# Sheet1.net
KiCad netlist of a schematic drawn in Altium Designer
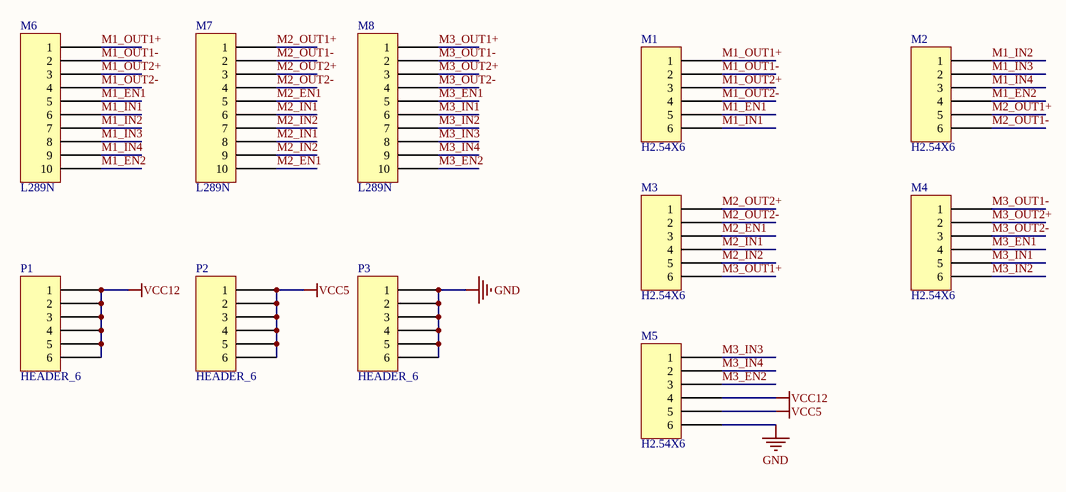
[diagram p0: Sheet1.SchDoc]

(export (version "E")
  (design (tool "Eeschema 10.0.6"))
  (components
    (comp (ref "M1") (value "H2.54X6") (footprint "Header6") (libsource (lib "Schlib1") (part "H2.54X6")))
    (comp (ref "M2") (value "H2.54X6") (footprint "Header6") (libsource (lib "Schlib1") (part "H2.54X6")))
    (comp (ref "M3") (value "H2.54X6") (footprint "Header6") (libsource (lib "Schlib1") (part "H2.54X6")))
    (comp (ref "M4") (value "H2.54X6") (footprint "Header6") (libsource (lib "Schlib1") (part "H2.54X6")))
    (comp (ref "M5") (value "H2.54X6") (footprint "Header6") (libsource (lib "Schlib1") (part "H2.54X6")))
    (comp (ref "M6") (value "L289N") (footprint "HDR1X10") (libsource (lib "Schlib1") (part "L289N")))
    (comp (ref "M7") (value "L289N") (footprint "HDR1X10") (libsource (lib "Schlib1") (part "L289N")))
    (comp (ref "M8") (value "L289N") (footprint "HDR1X10") (libsource (lib "Schlib1") (part "L289N")))
    (comp (ref "P1") (value "HEADER_6") (footprint "HDR1X6") (libsource (lib "Schlib1") (part "HEADER_6")))
    (comp (ref "P2") (value "HEADER_6") (footprint "HDR1X6") (libsource (lib "Schlib1") (part "HEADER_6")))
    (comp (ref "P3") (value "HEADER_6") (footprint "HDR1X6") (libsource (lib "Schlib1") (part "HEADER_6")))
  )
  (nets
    (net (code "1") (name "/M1_EN1") (class "Default")
      (node (ref "M1") (pin "5") (pinfunction "5_5") (pintype "passive"))
      (node (ref "M6") (pin "5") (pinfunction "5_5") (pintype "passive"))
    )
    (net (code "2") (name "/M1_EN2") (class "Default")
      (node (ref "M2") (pin "4") (pinfunction "4_4") (pintype "passive"))
      (node (ref "M6") (pin "10") (pinfunction "10_10") (pintype "passive"))
    )
    (net (code "3") (name "/M1_IN1") (class "Default")
      (node (ref "M1") (pin "6") (pinfunction "6_6") (pintype "passive"))
      (node (ref "M6") (pin "6") (pinfunction "6_6") (pintype "passive"))
    )
    (net (code "4") (name "/M1_IN2") (class "Default")
      (node (ref "M2") (pin "1") (pinfunction "1_1") (pintype "passive"))
      (node (ref "M6") (pin "7") (pinfunction "7_7") (pintype "passive"))
    )
    (net (code "5") (name "/M1_IN3") (class "Default")
      (node (ref "M2") (pin "2") (pinfunction "2_2") (pintype "passive"))
      (node (ref "M6") (pin "8") (pinfunction "8_8") (pintype "passive"))
    )
    (net (code "6") (name "/M1_IN4") (class "Default")
      (node (ref "M2") (pin "3") (pinfunction "3_3") (pintype "passive"))
      (node (ref "M6") (pin "9") (pinfunction "9_9") (pintype "passive"))
    )
    (net (code "7") (name "/M1_OUT1+") (class "Default")
      (node (ref "M1") (pin "1") (pinfunction "1_1") (pintype "passive"))
      (node (ref "M6") (pin "1") (pinfunction "1_1") (pintype "passive"))
    )
    (net (code "8") (name "/M1_OUT1-") (class "Default")
      (node (ref "M1") (pin "2") (pinfunction "2_2") (pintype "passive"))
      (node (ref "M6") (pin "2") (pinfunction "2_2") (pintype "passive"))
    )
    (net (code "9") (name "/M1_OUT2+") (class "Default")
      (node (ref "M1") (pin "3") (pinfunction "3_3") (pintype "passive"))
      (node (ref "M6") (pin "3") (pinfunction "3_3") (pintype "passive"))
    )
    (net (code "10") (name "/M1_OUT2-") (class "Default")
      (node (ref "M1") (pin "4") (pinfunction "4_4") (pintype "passive"))
      (node (ref "M6") (pin "4") (pinfunction "4_4") (pintype "passive"))
    )
    (net (code "11") (name "/M2_EN1") (class "Default")
      (node (ref "M3") (pin "3") (pinfunction "3_3") (pintype "passive"))
      (node (ref "M7") (pin "10") (pinfunction "10_10") (pintype "passive"))
      (node (ref "M7") (pin "5") (pinfunction "5_5") (pintype "passive"))
    )
    (net (code "12") (name "/M2_IN1") (class "Default")
      (node (ref "M3") (pin "4") (pinfunction "4_4") (pintype "passive"))
      (node (ref "M7") (pin "6") (pinfunction "6_6") (pintype "passive"))
      (node (ref "M7") (pin "8") (pinfunction "8_8") (pintype "passive"))
    )
    (net (code "13") (name "/M2_IN2") (class "Default")
      (node (ref "M3") (pin "5") (pinfunction "5_5") (pintype "passive"))
      (node (ref "M7") (pin "7") (pinfunction "7_7") (pintype "passive"))
      (node (ref "M7") (pin "9") (pinfunction "9_9") (pintype "passive"))
    )
    (net (code "14") (name "/M2_OUT1+") (class "Default")
      (node (ref "M2") (pin "5") (pinfunction "5_5") (pintype "passive"))
      (node (ref "M7") (pin "1") (pinfunction "1_1") (pintype "passive"))
    )
    (net (code "15") (name "/M2_OUT1-") (class "Default")
      (node (ref "M2") (pin "6") (pinfunction "6_6") (pintype "passive"))
      (node (ref "M7") (pin "2") (pinfunction "2_2") (pintype "passive"))
    )
    (net (code "16") (name "/M2_OUT2+") (class "Default")
      (node (ref "M3") (pin "1") (pinfunction "1_1") (pintype "passive"))
      (node (ref "M7") (pin "3") (pinfunction "3_3") (pintype "passive"))
    )
    (net (code "17") (name "/M2_OUT2-") (class "Default")
      (node (ref "M3") (pin "2") (pinfunction "2_2") (pintype "passive"))
      (node (ref "M7") (pin "4") (pinfunction "4_4") (pintype "passive"))
    )
    (net (code "18") (name "/M3_EN1") (class "Default")
      (node (ref "M4") (pin "4") (pinfunction "4_4") (pintype "passive"))
      (node (ref "M8") (pin "5") (pinfunction "5_5") (pintype "passive"))
    )
    (net (code "19") (name "/M3_EN2") (class "Default")
      (node (ref "M5") (pin "3") (pinfunction "3_3") (pintype "passive"))
      (node (ref "M8") (pin "10") (pinfunction "10_10") (pintype "passive"))
    )
    (net (code "20") (name "/M3_IN1") (class "Default")
      (node (ref "M4") (pin "5") (pinfunction "5_5") (pintype "passive"))
      (node (ref "M8") (pin "6") (pinfunction "6_6") (pintype "passive"))
    )
    (net (code "21") (name "/M3_IN2") (class "Default")
      (node (ref "M4") (pin "6") (pinfunction "6_6") (pintype "passive"))
      (node (ref "M8") (pin "7") (pinfunction "7_7") (pintype "passive"))
    )
    (net (code "22") (name "/M3_IN3") (class "Default")
      (node (ref "M5") (pin "1") (pinfunction "1_1") (pintype "passive"))
      (node (ref "M8") (pin "8") (pinfunction "8_8") (pintype "passive"))
    )
    (net (code "23") (name "/M3_IN4") (class "Default")
      (node (ref "M5") (pin "2") (pinfunction "2_2") (pintype "passive"))
      (node (ref "M8") (pin "9") (pinfunction "9_9") (pintype "passive"))
    )
    (net (code "24") (name "/M3_OUT1+") (class "Default")
      (node (ref "M3") (pin "6") (pinfunction "6_6") (pintype "passive"))
      (node (ref "M8") (pin "1") (pinfunction "1_1") (pintype "passive"))
    )
    (net (code "25") (name "/M3_OUT1-") (class "Default")
      (node (ref "M4") (pin "1") (pinfunction "1_1") (pintype "passive"))
      (node (ref "M8") (pin "2") (pinfunction "2_2") (pintype "passive"))
    )
    (net (code "26") (name "/M3_OUT2+") (class "Default")
      (node (ref "M4") (pin "2") (pinfunction "2_2") (pintype "passive"))
      (node (ref "M8") (pin "3") (pinfunction "3_3") (pintype "passive"))
    )
    (net (code "27") (name "/M3_OUT2-") (class "Default")
      (node (ref "M4") (pin "3") (pinfunction "3_3") (pintype "passive"))
      (node (ref "M8") (pin "4") (pinfunction "4_4") (pintype "passive"))
    )
    (net (code "28") (name "GND") (class "Default")
      (node (ref "M5") (pin "6") (pinfunction "6_6") (pintype "passive"))
      (node (ref "P3") (pin "1") (pinfunction "1_1") (pintype "passive"))
      (node (ref "P3") (pin "2") (pinfunction "2_2") (pintype "passive"))
      (node (ref "P3") (pin "3") (pinfunction "3_3") (pintype "passive"))
      (node (ref "P3") (pin "4") (pinfunction "4_4") (pintype "passive"))
      (node (ref "P3") (pin "5") (pinfunction "5_5") (pintype "passive"))
      (node (ref "P3") (pin "6") (pinfunction "6_6") (pintype "passive"))
    )
    (net (code "29") (name "VCC5") (class "Default")
      (node (ref "M5") (pin "5") (pinfunction "5_5") (pintype "passive"))
      (node (ref "P2") (pin "1") (pinfunction "1_1") (pintype "passive"))
      (node (ref "P2") (pin "2") (pinfunction "2_2") (pintype "passive"))
      (node (ref "P2") (pin "3") (pinfunction "3_3") (pintype "passive"))
      (node (ref "P2") (pin "4") (pinfunction "4_4") (pintype "passive"))
      (node (ref "P2") (pin "5") (pinfunction "5_5") (pintype "passive"))
      (node (ref "P2") (pin "6") (pinfunction "6_6") (pintype "passive"))
    )
    (net (code "30") (name "VCC12") (class "Default")
      (node (ref "M5") (pin "4") (pinfunction "4_4") (pintype "passive"))
      (node (ref "P1") (pin "1") (pinfunction "1_1") (pintype "passive"))
      (node (ref "P1") (pin "2") (pinfunction "2_2") (pintype "passive"))
      (node (ref "P1") (pin "3") (pinfunction "3_3") (pintype "passive"))
      (node (ref "P1") (pin "4") (pinfunction "4_4") (pintype "passive"))
      (node (ref "P1") (pin "5") (pinfunction "5_5") (pintype "passive"))
      (node (ref "P1") (pin "6") (pinfunction "6_6") (pintype "passive"))
    )
  )
)
